# Teensylu.net
KiCad netlist of a schematic drawn in EAGLE
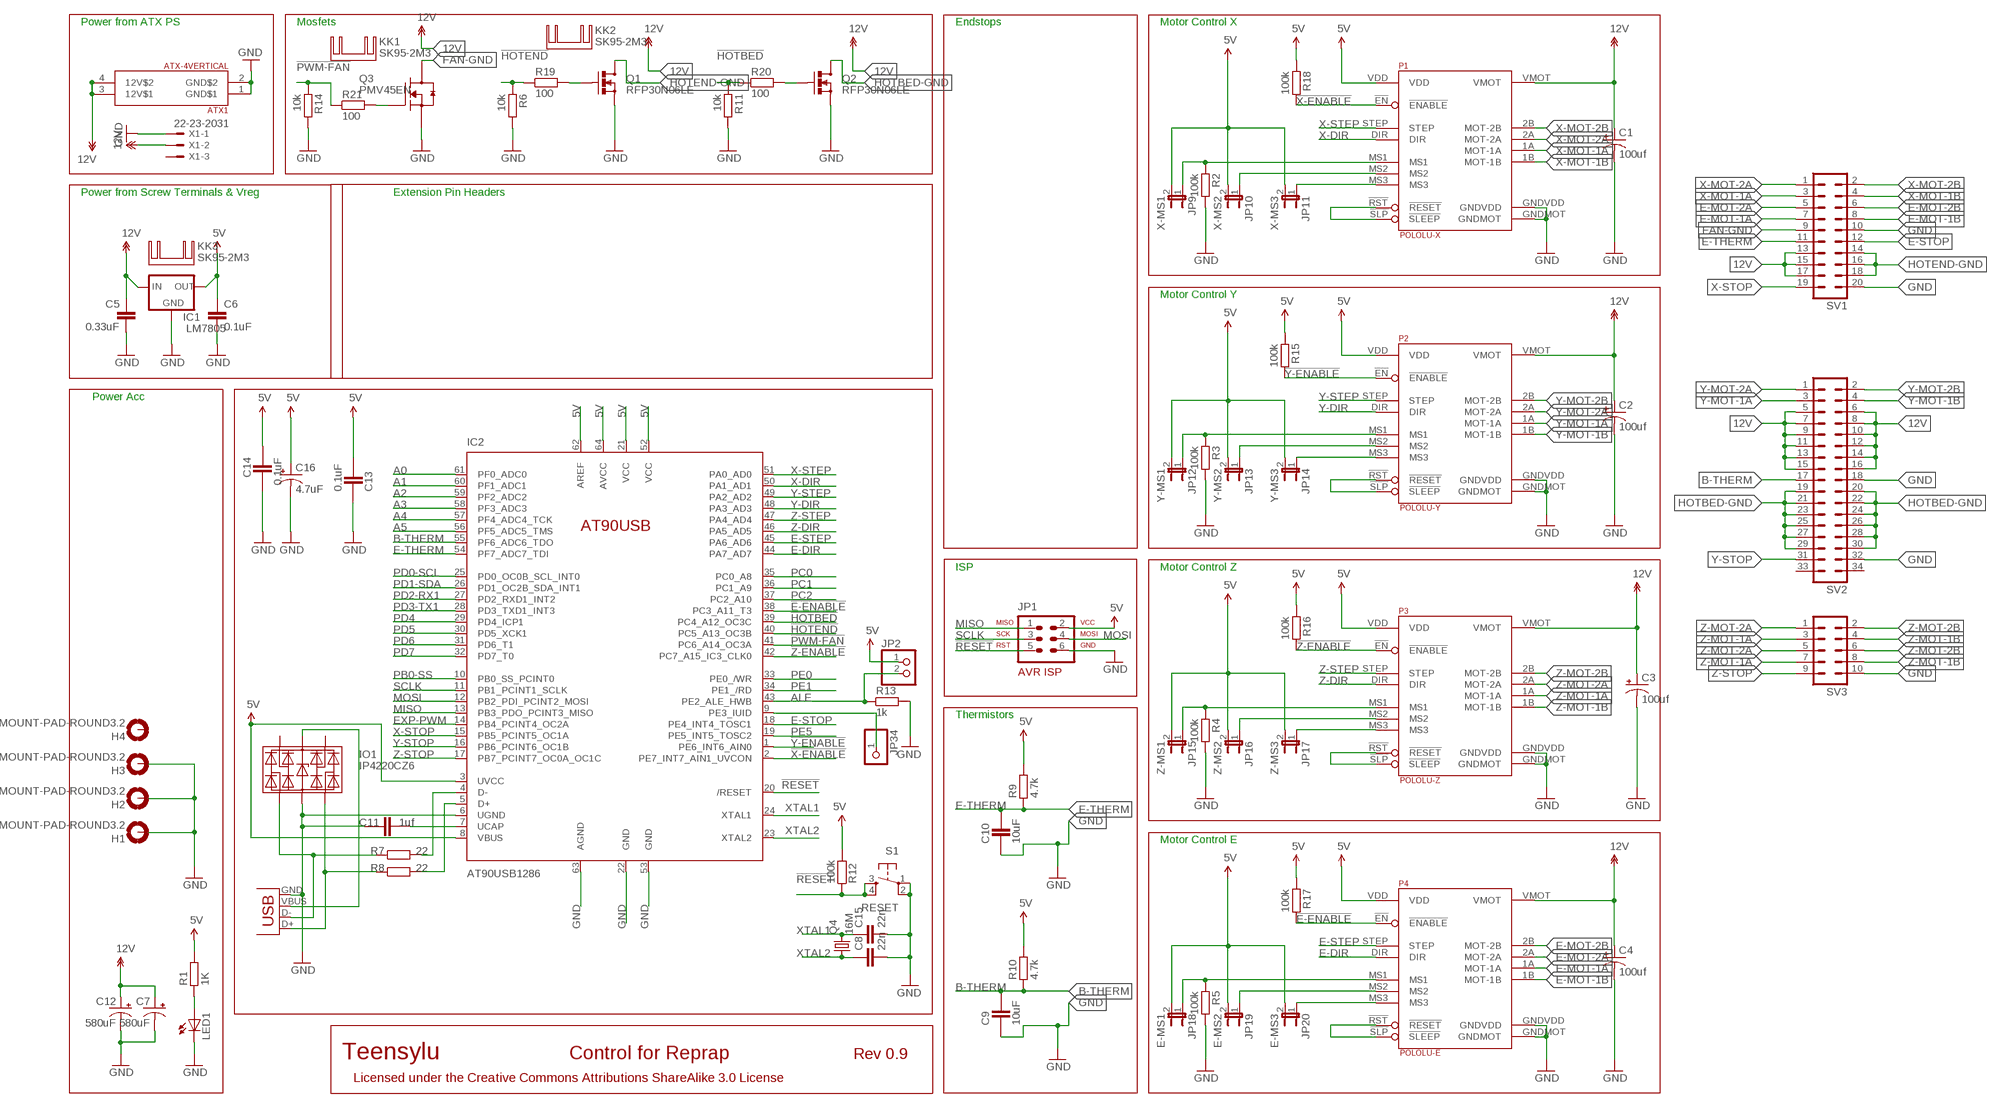
[diagram p0: schematic, sheet 1]

(export (version "E")
  (design (tool "Eeschema 10.0.6"))
  (components
    (comp (ref "ATX1")
      (value "ATX-4VERTICAL")
      (footprint "eagle-import:MINIFITJR-4-VERTICAL")
      (libsource (lib "eagle-import") (part "ATX-4VERTICAL"))
    )
    (comp (ref "C1")
      (value "100uf")
      (footprint "eagle-import:CPOL-RADIAL-100UF-25V")
      (libsource (lib "eagle-import") (part "CAP_POLPTH1"))
    )
    (comp (ref "C2")
      (value "100uf")
      (footprint "eagle-import:CPOL-RADIAL-100UF-25V")
      (libsource (lib "eagle-import") (part "CAP_POLPTH1"))
    )
    (comp (ref "C3")
      (value "100uf")
      (footprint "eagle-import:CPOL-RADIAL-100UF-25V")
      (libsource (lib "eagle-import") (part "CAP_POLPTH1"))
    )
    (comp (ref "C4")
      (value "100uf")
      (footprint "eagle-import:CPOL-RADIAL-100UF-25V")
      (libsource (lib "eagle-import") (part "CAP_POLPTH1"))
    )
    (comp (ref "C5")
      (value "0.33uF")
      (footprint "eagle-import:CAP-PTH-SMALL2")
      (libsource (lib "eagle-import") (part "CAPPTH2"))
    )
    (comp (ref "C6")
      (value "0.1uF")
      (footprint "eagle-import:CAP-PTH-SMALL2")
      (libsource (lib "eagle-import") (part "CAPPTH2"))
    )
    (comp (ref "C7")
      (value "580uF")
      (footprint "eagle-import:CPOL-RADIAL-1000UF-25V")
      (libsource (lib "eagle-import") (part "CAP_POLPTH4"))
    )
    (comp (ref "C8")
      (value "22n")
      (footprint "eagle-import:C0603")
      (libsource (lib "eagle-import") (part "C-EUC0603"))
    )
    (comp (ref "C9")
      (value "10uF")
      (footprint "eagle-import:CAPC1608X92N")
      (libsource (lib "eagle-import") (part "CAPACITOR_0603"))
    )
    (comp (ref "C10")
      (value "10uF")
      (footprint "eagle-import:CAPC1608X92N")
      (libsource (lib "eagle-import") (part "CAPACITOR_0603"))
    )
    (comp (ref "C11")
      (value "1uf")
      (footprint "eagle-import:CAPC1608X92N")
      (libsource (lib "eagle-import") (part "CAPACITOR_0603"))
    )
    (comp (ref "C12")
      (value "580uF")
      (footprint "eagle-import:CPOL-RADIAL-1000UF-25V")
      (libsource (lib "eagle-import") (part "CAP_POLPTH4"))
    )
    (comp (ref "C13")
      (value "0.1uF")
      (footprint "eagle-import:CAPC1608X92N")
      (libsource (lib "eagle-import") (part "CAPACITOR_0603"))
    )
    (comp (ref "C14")
      (value "0.1uF")
      (footprint "eagle-import:CAPC1608X92N")
      (libsource (lib "eagle-import") (part "CAPACITOR_0603"))
    )
    (comp (ref "C15")
      (value "22n")
      (footprint "eagle-import:C0603")
      (libsource (lib "eagle-import") (part "C-EUC0603"))
    )
    (comp (ref "C16")
      (value "4.7uF")
      (footprint "eagle-import:CPOL-RADIAL-10UF-25V")
      (libsource (lib "eagle-import") (part "CAP_POLPTH2"))
    )
    (comp (ref "H1")
      (value "MOUNT-PAD-ROUND3.2")
      (footprint "eagle-import:3,2-PAD")
      (libsource (lib "eagle-import") (part "MOUNT-PAD-ROUND3.2"))
    )
    (comp (ref "H2")
      (value "MOUNT-PAD-ROUND3.2")
      (footprint "eagle-import:3,2-PAD")
      (libsource (lib "eagle-import") (part "MOUNT-PAD-ROUND3.2"))
    )
    (comp (ref "H3")
      (value "MOUNT-PAD-ROUND3.2")
      (footprint "eagle-import:3,2-PAD")
      (libsource (lib "eagle-import") (part "MOUNT-PAD-ROUND3.2"))
    )
    (comp (ref "H4")
      (value "MOUNT-PAD-ROUND3.2")
      (footprint "eagle-import:3,2-PAD")
      (libsource (lib "eagle-import") (part "MOUNT-PAD-ROUND3.2"))
    )
    (comp (ref "IC1")
      (value "LM7805")
      (footprint "eagle-import:78XXL-CUSTOM")
      (libsource (lib "eagle-import") (part "V_REG_78XX"))
    )
    (comp (ref "IC2")
      (value "AT90USB1286")
      (footprint "eagle-import:TQFP64-2")
      (libsource (lib "eagle-import") (part "AT90USB"))
    )
    (comp (ref "IO1")
      (value "IP4220CZ6")
      (footprint "eagle-import:SOT23-6")
      (libsource (lib "eagle-import") (part "IP4220CZ6"))
    )
    (comp (ref "J1")
      (value "USB")
      (footprint "eagle-import:USB-B-PTH")
      (libsource (lib "eagle-import") (part "USBPTH"))
    )
    (comp (ref "JP1")
      (value "AVR-ISP-6VERT")
      (footprint "eagle-import:AVR-ISP-6")
      (libsource (lib "eagle-import") (part "AVR-ISP-6VERT"))
    )
    (comp (ref "JP2")
      (value "PINHD-1X2")
      (footprint "eagle-import:1X02")
      (libsource (lib "eagle-import") (part "PINHD-1X2"))
    )
    (comp (ref "JP9")
      (value "X-MS1")
      (footprint "eagle-import:1X02")
      (libsource (lib "eagle-import") (part "JUMPER-2PTH"))
    )
    (comp (ref "JP10")
      (value "X-MS2")
      (footprint "eagle-import:1X02")
      (libsource (lib "eagle-import") (part "JUMPER-2PTH"))
    )
    (comp (ref "JP11")
      (value "X-MS3")
      (footprint "eagle-import:1X02")
      (libsource (lib "eagle-import") (part "JUMPER-2PTH"))
    )
    (comp (ref "JP12")
      (value "Y-MS1")
      (footprint "eagle-import:1X02")
      (libsource (lib "eagle-import") (part "JUMPER-2PTH"))
    )
    (comp (ref "JP13")
      (value "Y-MS2")
      (footprint "eagle-import:1X02")
      (libsource (lib "eagle-import") (part "JUMPER-2PTH"))
    )
    (comp (ref "JP14")
      (value "Y-MS3")
      (footprint "eagle-import:1X02")
      (libsource (lib "eagle-import") (part "JUMPER-2PTH"))
    )
    (comp (ref "JP15")
      (value "Z-MS1")
      (footprint "eagle-import:1X02")
      (libsource (lib "eagle-import") (part "JUMPER-2PTH"))
    )
    (comp (ref "JP16")
      (value "Z-MS2")
      (footprint "eagle-import:1X02")
      (libsource (lib "eagle-import") (part "JUMPER-2PTH"))
    )
    (comp (ref "JP17")
      (value "Z-MS3")
      (footprint "eagle-import:1X02")
      (libsource (lib "eagle-import") (part "JUMPER-2PTH"))
    )
    (comp (ref "JP18")
      (value "E-MS1")
      (footprint "eagle-import:1X02")
      (libsource (lib "eagle-import") (part "JUMPER-2PTH"))
    )
    (comp (ref "JP19")
      (value "E-MS2")
      (footprint "eagle-import:1X02")
      (libsource (lib "eagle-import") (part "JUMPER-2PTH"))
    )
    (comp (ref "JP20")
      (value "E-MS3")
      (footprint "eagle-import:1X02")
      (libsource (lib "eagle-import") (part "JUMPER-2PTH"))
    )
    (comp (ref "JP34")
      (value "PINHD-1X1")
      (footprint "eagle-import:1X01")
      (libsource (lib "eagle-import") (part "PINHD-1X1"))
    )
    (comp (ref "KK1")
      (value "SK95-2M3")
      (footprint "eagle-import:SK95-2M3")
      (libsource (lib "eagle-import") (part "SK95-2M3"))
    )
    (comp (ref "KK2")
      (value "SK95-2M3")
      (footprint "eagle-import:SK95-2M3")
      (libsource (lib "eagle-import") (part "SK95-2M3"))
    )
    (comp (ref "KK3")
      (value "SK95-2M3")
      (footprint "eagle-import:SK95-2M3")
      (libsource (lib "eagle-import") (part "SK95-2M3"))
    )
    (comp (ref "LED1")
      (value "LED5MM")
      (footprint "eagle-import:LED5MM")
      (libsource (lib "eagle-import") (part "LED5MM"))
    )
    (comp (ref "P1")
      (value "POLOLU-X")
      (footprint "eagle-import:POLOLU-ALLEGRO-PTH")
      (libsource (lib "eagle-import") (part "POLOLU-ALLEGRO"))
    )
    (comp (ref "P2")
      (value "POLOLU-Y")
      (footprint "eagle-import:POLOLU-ALLEGRO-PTH")
      (libsource (lib "eagle-import") (part "POLOLU-ALLEGRO"))
    )
    (comp (ref "P3")
      (value "POLOLU-Z")
      (footprint "eagle-import:POLOLU-ALLEGRO-PTH")
      (libsource (lib "eagle-import") (part "POLOLU-ALLEGRO"))
    )
    (comp (ref "P4")
      (value "POLOLU-E")
      (footprint "eagle-import:POLOLU-ALLEGRO-PTH")
      (libsource (lib "eagle-import") (part "POLOLU-ALLEGRO"))
    )
    (comp (ref "Q1")
      (value "RFP30N06LE")
      (footprint "eagle-import:TO220V")
      (libsource (lib "eagle-import") (part "MOSFET-NCHANNELPTH2"))
    )
    (comp (ref "Q2")
      (value "RFP30N06LE")
      (footprint "eagle-import:TO220V")
      (libsource (lib "eagle-import") (part "MOSFET-NCHANNELPTH2"))
    )
    (comp (ref "Q3")
      (value "PMV45EN")
      (footprint "eagle-import:SOT95P280X135-3N")
      (libsource (lib "eagle-import") (part "MOSFET-NCH_SOT-23"))
    )
    (comp (ref "Q4")
      (value "16M")
      (footprint "eagle-import:HC49U-V")
      (libsource (lib "eagle-import") (part "CRYSTALHC49U-V"))
    )
    (comp (ref "R1")
      (value "1K")
      (footprint "eagle-import:RESC1608X55N")
      (libsource (lib "eagle-import") (part "RESISTOR_0603"))
    )
    (comp (ref "R2")
      (value "100k")
      (footprint "eagle-import:RESC1608X55N")
      (libsource (lib "eagle-import") (part "RESISTOR_0603"))
    )
    (comp (ref "R3")
      (value "100k")
      (footprint "eagle-import:RESC1608X55N")
      (libsource (lib "eagle-import") (part "RESISTOR_0603"))
    )
    (comp (ref "R4")
      (value "100k")
      (footprint "eagle-import:RESC1608X55N")
      (libsource (lib "eagle-import") (part "RESISTOR_0603"))
    )
    (comp (ref "R5")
      (value "100k")
      (footprint "eagle-import:RESC1608X55N")
      (libsource (lib "eagle-import") (part "RESISTOR_0603"))
    )
    (comp (ref "R6")
      (value "10k")
      (footprint "eagle-import:RESC1608X55N")
      (libsource (lib "eagle-import") (part "RESISTOR_0603"))
    )
    (comp (ref "R7")
      (value "22")
      (footprint "eagle-import:RESC1608X55N")
      (libsource (lib "eagle-import") (part "RESISTOR_0603"))
    )
    (comp (ref "R8")
      (value "22")
      (footprint "eagle-import:RESC1608X55N")
      (libsource (lib "eagle-import") (part "RESISTOR_0603"))
    )
    (comp (ref "R9")
      (value "4.7k")
      (footprint "eagle-import:RESC1608X55N")
      (libsource (lib "eagle-import") (part "RESISTOR_0603"))
    )
    (comp (ref "R10")
      (value "4.7k")
      (footprint "eagle-import:RESC1608X55N")
      (libsource (lib "eagle-import") (part "RESISTOR_0603"))
    )
    (comp (ref "R11")
      (value "10k")
      (footprint "eagle-import:RESC1608X55N")
      (libsource (lib "eagle-import") (part "RESISTOR_0603"))
    )
    (comp (ref "R12")
      (value "100k")
      (footprint "eagle-import:RESC1608X55N")
      (libsource (lib "eagle-import") (part "RESISTOR_0603"))
    )
    (comp (ref "R13")
      (value "1k")
      (footprint "eagle-import:RESC1608X55N")
      (libsource (lib "eagle-import") (part "RESISTOR_0603"))
    )
    (comp (ref "R14")
      (value "10k")
      (footprint "eagle-import:RESC1608X55N")
      (libsource (lib "eagle-import") (part "RESISTOR_0603"))
    )
    (comp (ref "R15")
      (value "100k")
      (footprint "eagle-import:RESC1608X55N")
      (libsource (lib "eagle-import") (part "RESISTOR_0603"))
    )
    (comp (ref "R16")
      (value "100k")
      (footprint "eagle-import:RESC1608X55N")
      (libsource (lib "eagle-import") (part "RESISTOR_0603"))
    )
    (comp (ref "R17")
      (value "100k")
      (footprint "eagle-import:RESC1608X55N")
      (libsource (lib "eagle-import") (part "RESISTOR_0603"))
    )
    (comp (ref "R18")
      (value "100k")
      (footprint "eagle-import:RESC1608X55N")
      (libsource (lib "eagle-import") (part "RESISTOR_0603"))
    )
    (comp (ref "R19")
      (value "100")
      (footprint "eagle-import:RESC1608X55N")
      (libsource (lib "eagle-import") (part "RESISTOR_0603"))
    )
    (comp (ref "R20")
      (value "100")
      (footprint "eagle-import:RESC1608X55N")
      (libsource (lib "eagle-import") (part "RESISTOR_0603"))
    )
    (comp (ref "R21")
      (value "100")
      (footprint "eagle-import:RESC1608X55N")
      (libsource (lib "eagle-import") (part "RESISTOR_0603"))
    )
    (comp (ref "S1")
      (value "RESET")
      (footprint "eagle-import:TACTILE-PTH")
      (libsource (lib "eagle-import") (part "TAC_SWITCHPTH"))
    )
    (comp (ref "SV1")
      (value "ML20L")
      (footprint "eagle-import:ML20L")
      (libsource (lib "eagle-import") (part "ML20L"))
    )
    (comp (ref "SV2")
      (value "ML34L")
      (footprint "eagle-import:ML34L")
      (libsource (lib "eagle-import") (part "ML34L"))
    )
    (comp (ref "SV3")
      (value "ML10L")
      (footprint "eagle-import:ML10L")
      (libsource (lib "eagle-import") (part "ML10L"))
    )
    (comp (ref "X1")
      (value "22-23-2031")
      (footprint "eagle-import:22-23-2031")
      (fields (field (name "MF") "MOLEX"))
      (libsource (lib "eagle-import") (part "22-23-2031"))
    )
  )
  (nets
    (net (code "1") (name "/A0") (class "Default")
      (node (ref "IC2") (pin "61") (pinfunction "PF0_ADC0_61") (pintype "bidirectional"))
    )
    (net (code "2") (name "/A1") (class "Default")
      (node (ref "IC2") (pin "60") (pinfunction "PF1_ADC1_60") (pintype "bidirectional"))
    )
    (net (code "3") (name "/A2") (class "Default")
      (node (ref "IC2") (pin "59") (pinfunction "PF2_ADC2_59") (pintype "bidirectional"))
    )
    (net (code "4") (name "/A3") (class "Default")
      (node (ref "IC2") (pin "58") (pinfunction "PF3_ADC3_58") (pintype "bidirectional"))
    )
    (net (code "5") (name "/A4") (class "Default")
      (node (ref "IC2") (pin "57") (pinfunction "PF4_ADC4_TCK_57") (pintype "bidirectional"))
    )
    (net (code "6") (name "/A5") (class "Default")
      (node (ref "IC2") (pin "56") (pinfunction "PF5_ADC5_TMS_56") (pintype "bidirectional"))
    )
    (net (code "7") (name "/ALE") (class "Default")
      (node (ref "IC2") (pin "43") (pinfunction "PE2_ALE_HWB_43") (pintype "bidirectional"))
      (node (ref "JP2") (pin "2") (pinfunction "2_2") (pintype "passive"))
      (node (ref "R13") (pin "1") (pinfunction "1_1") (pintype "passive"))
    )
    (net (code "8") (name "/E-DIR") (class "Default")
      (node (ref "IC2") (pin "44") (pinfunction "PA7_AD7_44") (pintype "bidirectional"))
      (node (ref "P4") (pin "DIR") (pinfunction "DIR_DIR") (pintype "bidirectional"))
    )
    (net (code "9") (name "/E-STEP") (class "Default")
      (node (ref "IC2") (pin "45") (pinfunction "PA6_AD6_45") (pintype "bidirectional"))
      (node (ref "P4") (pin "STEP") (pinfunction "STEP_STEP") (pintype "bidirectional"))
    )
    (net (code "10") (name "/EXP-PWM") (class "Default")
      (node (ref "IC2") (pin "14") (pinfunction "PB4_PCINT4_OC2A_14") (pintype "bidirectional"))
    )
    (net (code "11") (name "/MISO") (class "Default")
      (node (ref "IC2") (pin "13") (pinfunction "PB3_PDO_PCINT3_MISO_13") (pintype "bidirectional"))
      (node (ref "JP1") (pin "1") (pinfunction "1_1") (pintype "passive"))
    )
    (net (code "12") (name "/MOSI") (class "Default")
      (node (ref "IC2") (pin "12") (pinfunction "PB2_PDI_PCINT2_MOSI_12") (pintype "bidirectional"))
      (node (ref "JP1") (pin "4") (pinfunction "4_4") (pintype "passive"))
    )
    (net (code "13") (name "/PB0-SS") (class "Default")
      (node (ref "IC2") (pin "10") (pinfunction "PB0_SS_PCINT0_10") (pintype "bidirectional"))
    )
    (net (code "14") (name "/PC0") (class "Default")
      (node (ref "IC2") (pin "35") (pinfunction "PC0_A8_35") (pintype "bidirectional"))
    )
    (net (code "15") (name "/PC1") (class "Default")
      (node (ref "IC2") (pin "36") (pinfunction "PC1_A9_36") (pintype "bidirectional"))
    )
    (net (code "16") (name "/PC2") (class "Default")
      (node (ref "IC2") (pin "37") (pinfunction "PC2_A10_37") (pintype "bidirectional"))
    )
    (net (code "17") (name "/PD0-SCL") (class "Default")
      (node (ref "IC2") (pin "25") (pinfunction "PD0_OC0B_SCL_INT0_25") (pintype "bidirectional"))
    )
    (net (code "18") (name "/PD1-SDA") (class "Default")
      (node (ref "IC2") (pin "26") (pinfunction "PD1_OC2B_SDA_INT1_26") (pintype "bidirectional"))
    )
    (net (code "19") (name "/PD2-RX1") (class "Default")
      (node (ref "IC2") (pin "27") (pinfunction "PD2_RXD1_INT2_27") (pintype "bidirectional"))
    )
    (net (code "20") (name "/PD3-TX1") (class "Default")
      (node (ref "IC2") (pin "28") (pinfunction "PD3_TXD1_INT3_28") (pintype "bidirectional"))
    )
    (net (code "21") (name "/PD4") (class "Default")
      (node (ref "IC2") (pin "29") (pinfunction "PD4_ICP1_29") (pintype "bidirectional"))
    )
    (net (code "22") (name "/PD5") (class "Default")
      (node (ref "IC2") (pin "30") (pinfunction "PD5_XCK1_30") (pintype "bidirectional"))
    )
    (net (code "23") (name "/PD6") (class "Default")
      (node (ref "IC2") (pin "31") (pinfunction "PD6_T1_31") (pintype "bidirectional"))
    )
    (net (code "24") (name "/PD7") (class "Default")
      (node (ref "IC2") (pin "32") (pinfunction "PD7_T0_32") (pintype "bidirectional"))
    )
    (net (code "25") (name "/PE0") (class "Default")
      (node (ref "IC2") (pin "33") (pinfunction "PE0_/WR_33") (pintype "bidirectional"))
    )
    (net (code "26") (name "/PE1") (class "Default")
      (node (ref "IC2") (pin "34") (pinfunction "PE1_/RD_34") (pintype "bidirectional"))
    )
    (net (code "27") (name "/PE5") (class "Default")
      (node (ref "IC2") (pin "19") (pinfunction "PE5_INT5_TOSC2_19") (pintype "bidirectional"))
    )
    (net (code "28") (name "/SCLK") (class "Default")
      (node (ref "IC2") (pin "11") (pinfunction "PB1_PCINT1_SCLK_11") (pintype "bidirectional"))
      (node (ref "JP1") (pin "3") (pinfunction "3_3") (pintype "passive"))
    )
    (net (code "29") (name "/X-DIR") (class "Default")
      (node (ref "IC2") (pin "50") (pinfunction "PA1_AD1_50") (pintype "bidirectional"))
      (node (ref "P1") (pin "DIR") (pinfunction "DIR_DIR") (pintype "bidirectional"))
    )
    (net (code "30") (name "/X-STEP") (class "Default")
      (node (ref "IC2") (pin "51") (pinfunction "PA0_AD0_51") (pintype "bidirectional"))
      (node (ref "P1") (pin "STEP") (pinfunction "STEP_STEP") (pintype "bidirectional"))
    )
    (net (code "31") (name "/XTAL1") (class "Default")
      (node (ref "C15") (pin "1") (pinfunction "1_1") (pintype "passive"))
      (node (ref "IC2") (pin "24") (pinfunction "XTAL1_24") (pintype "passive"))
      (node (ref "Q4") (pin "2") (pinfunction "2_2") (pintype "passive"))
    )
    (net (code "32") (name "/XTAL2") (class "Default")
      (node (ref "C8") (pin "1") (pinfunction "1_1") (pintype "passive"))
      (node (ref "IC2") (pin "23") (pinfunction "XTAL2_23") (pintype "passive"))
      (node (ref "Q4") (pin "1") (pinfunction "1_1") (pintype "passive"))
    )
    (net (code "33") (name "/Y-DIR") (class "Default")
      (node (ref "IC2") (pin "48") (pinfunction "PA3_AD3_48") (pintype "bidirectional"))
      (node (ref "P2") (pin "DIR") (pinfunction "DIR_DIR") (pintype "bidirectional"))
    )
    (net (code "34") (name "/Y-STEP") (class "Default")
      (node (ref "IC2") (pin "49") (pinfunction "PA2_AD2_49") (pintype "bidirectional"))
      (node (ref "P2") (pin "STEP") (pinfunction "STEP_STEP") (pintype "bidirectional"))
    )
    (net (code "35") (name "/Z-DIR") (class "Default")
      (node (ref "IC2") (pin "46") (pinfunction "PA5_AD5_46") (pintype "bidirectional"))
      (node (ref "P3") (pin "DIR") (pinfunction "DIR_DIR") (pintype "bidirectional"))
    )
    (net (code "36") (name "/Z-STEP") (class "Default")
      (node (ref "IC2") (pin "47") (pinfunction "PA4_AD4_47") (pintype "bidirectional"))
      (node (ref "P3") (pin "STEP") (pinfunction "STEP_STEP") (pintype "bidirectional"))
    )
    (net (code "37") (name "/~{E-ENABLE}") (class "Default")
      (node (ref "IC2") (pin "38") (pinfunction "PC3_A11_T3_38") (pintype "bidirectional"))
      (node (ref "P4") (pin "!EN") (pinfunction "~{ENABLE}_!EN") (pintype "input"))
      (node (ref "R17") (pin "2") (pinfunction "2_2") (pintype "passive"))
    )
    (net (code "38") (name "/~{HOTBED}") (class "Default")
      (node (ref "IC2") (pin "39") (pinfunction "PC4_A12_OC3C_39") (pintype "bidirectional"))
      (node (ref "R11") (pin "1") (pinfunction "1_1") (pintype "passive"))
      (node (ref "R20") (pin "1") (pinfunction "1_1") (pintype "passive"))
    )
    (net (code "39") (name "/~{HOTEND}") (class "Default")
      (node (ref "IC2") (pin "40") (pinfunction "PC5_A13_OC3B_40") (pintype "bidirectional"))
      (node (ref "R19") (pin "1") (pinfunction "1_1") (pintype "passive"))
      (node (ref "R6") (pin "1") (pinfunction "1_1") (pintype "passive"))
    )
    (net (code "40") (name "/~{PWM-FAN}") (class "Default")
      (node (ref "IC2") (pin "41") (pinfunction "PC6_A14_OC3A_41") (pintype "bidirectional"))
      (node (ref "R14") (pin "1") (pinfunction "1_1") (pintype "passive"))
      (node (ref "R21") (pin "1") (pinfunction "1_1") (pintype "passive"))
    )
    (net (code "41") (name "/~{RESET}") (class "Default")
      (node (ref "IC2") (pin "20") (pinfunction "/RESET_20") (pintype "bidirectional"))
      (node (ref "JP1") (pin "5") (pinfunction "5_5") (pintype "passive"))
      (node (ref "R12") (pin "1") (pinfunction "1_1") (pintype "passive"))
      (node (ref "S1") (pin "3") (pinfunction "3_3") (pintype "passive"))
      (node (ref "S1") (pin "4") (pinfunction "4_4") (pintype "passive"))
    )
    (net (code "42") (name "/~{X-ENABLE}") (class "Default")
      (node (ref "IC2") (pin "2") (pinfunction "PE7_INT7_AIN1_UVCON_2") (pintype "bidirectional"))
      (node (ref "P1") (pin "!EN") (pinfunction "~{ENABLE}_!EN") (pintype "input"))
      (node (ref "R18") (pin "2") (pinfunction "2_2") (pintype "passive"))
    )
    (net (code "43") (name "/~{Y-ENABLE}") (class "Default")
      (node (ref "IC2") (pin "1") (pinfunction "PE6_INT6_AIN0_1") (pintype "bidirectional"))
      (node (ref "P2") (pin "!EN") (pinfunction "~{ENABLE}_!EN") (pintype "input"))
      (node (ref "R15") (pin "2") (pinfunction "2_2") (pintype "passive"))
    )
    (net (code "44") (name "/~{Z-ENABLE}") (class "Default")
      (node (ref "IC2") (pin "42") (pinfunction "PC7_A15_IC3_CLK0_42") (pintype "bidirectional"))
      (node (ref "P3") (pin "!EN") (pinfunction "~{ENABLE}_!EN") (pintype "input"))
      (node (ref "R16") (pin "2") (pinfunction "2_2") (pintype "passive"))
    )
    (net (code "45") (name "5V") (class "Default")
      (node (ref "C13") (pin "2") (pinfunction "2_2") (pintype "passive"))
      (node (ref "C14") (pin "1") (pinfunction "1_1") (pintype "passive"))
      (node (ref "C16") (pin "1") (pinfunction "+_1") (pintype "passive"))
      (node (ref "C6") (pin "1") (pinfunction "1_1") (pintype "passive"))
      (node (ref "IC1") (pin "OUT") (pinfunction "OUT_OUT") (pintype "output"))
      (node (ref "IC2") (pin "21") (pinfunction "VCC_21") (pintype "power_in"))
      (node (ref "IC2") (pin "3") (pinfunction "UVCC_3") (pintype "power_in"))
      (node (ref "IC2") (pin "52") (pinfunction "VCC_52") (pintype "power_in"))
      (node (ref "IC2") (pin "62") (pinfunction "AREF_62") (pintype "power_in"))
      (node (ref "IC2") (pin "64") (pinfunction "AVCC_64") (pintype "power_in"))
      (node (ref "IC2") (pin "8") (pinfunction "VBUS_8") (pintype "bidirectional"))
      (node (ref "JP1") (pin "2") (pinfunction "2_2") (pintype "passive"))
      (node (ref "JP10") (pin "2") (pinfunction "2_2") (pintype "passive"))
      (node (ref "JP11") (pin "2") (pinfunction "2_2") (pintype "passive"))
      (node (ref "JP12") (pin "2") (pinfunction "2_2") (pintype "passive"))
      (node (ref "JP13") (pin "2") (pinfunction "2_2") (pintype "passive"))
      (node (ref "JP14") (pin "2") (pinfunction "2_2") (pintype "passive"))
      (node (ref "JP15") (pin "2") (pinfunction "2_2") (pintype "passive"))
      (node (ref "JP16") (pin "2") (pinfunction "2_2") (pintype "passive"))
      (node (ref "JP17") (pin "2") (pinfunction "2_2") (pintype "passive"))
      (node (ref "JP18") (pin "2") (pinfunction "2_2") (pintype "passive"))
      (node (ref "JP19") (pin "2") (pinfunction "2_2") (pintype "passive"))
      (node (ref "JP2") (pin "1") (pinfunction "1_1") (pintype "passive"))
      (node (ref "JP20") (pin "2") (pinfunction "2_2") (pintype "passive"))
      (node (ref "JP9") (pin "2") (pinfunction "2_2") (pintype "passive"))
      (node (ref "P1") (pin "VDD") (pinfunction "VDD_VDD") (pintype "power_in"))
      (node (ref "P2") (pin "VDD") (pinfunction "VDD_VDD") (pintype "power_in"))
      (node (ref "P3") (pin "VDD") (pinfunction "VDD_VDD") (pintype "power_in"))
      (node (ref "P4") (pin "VDD") (pinfunction "VDD_VDD") (pintype "power_in"))
      (node (ref "R1") (pin "2") (pinfunction "2_2") (pintype "passive"))
      (node (ref "R10") (pin "2") (pinfunction "2_2") (pintype "passive"))
      (node (ref "R12") (pin "2") (pinfunction "2_2") (pintype "passive"))
      (node (ref "R15") (pin "1") (pinfunction "1_1") (pintype "passive"))
      (node (ref "R16") (pin "1") (pinfunction "1_1") (pintype "passive"))
      (node (ref "R17") (pin "1") (pinfunction "1_1") (pintype "passive"))
      (node (ref "R18") (pin "1") (pinfunction "1_1") (pintype "passive"))
      (node (ref "R9") (pin "2") (pinfunction "2_2") (pintype "passive"))
    )
    (net (code "46") (name "12V") (class "Default")
      (node (ref "ATX1") (pin "3") (pinfunction "12V$1_3") (pintype "power_in"))
      (node (ref "ATX1") (pin "4") (pinfunction "12V$2_4") (pintype "power_in"))
      (node (ref "C1") (pin "1") (pinfunction "+_1") (pintype "passive"))
      (node (ref "C12") (pin "1") (pinfunction "+_1") (pintype "passive"))
      (node (ref "C2") (pin "1") (pinfunction "+_1") (pintype "passive"))
      (node (ref "C3") (pin "1") (pinfunction "+_1") (pintype "passive"))
      (node (ref "C4") (pin "1") (pinfunction "+_1") (pintype "passive"))
      (node (ref "C5") (pin "1") (pinfunction "1_1") (pintype "passive"))
      (node (ref "C7") (pin "1") (pinfunction "+_1") (pintype "passive"))
      (node (ref "IC1") (pin "IN") (pinfunction "IN_IN") (pintype "input"))
      (node (ref "P1") (pin "VMOT") (pinfunction "VMOT_VMOT") (pintype "power_in"))
      (node (ref "P2") (pin "VMOT") (pinfunction "VMOT_VMOT") (pintype "power_in"))
      (node (ref "P3") (pin "VMOT") (pinfunction "VMOT_VMOT") (pintype "power_in"))
      (node (ref "P4") (pin "VMOT") (pinfunction "VMOT_VMOT") (pintype "power_in"))
      (node (ref "SV1") (pin "13") (pinfunction "13_13") (pintype "passive"))
      (node (ref "SV1") (pin "15") (pinfunction "15_15") (pintype "passive"))
      (node (ref "SV1") (pin "17") (pinfunction "17_17") (pintype "passive"))
      (node (ref "SV2") (pin "10") (pinfunction "10_10") (pintype "passive"))
      (node (ref "SV2") (pin "11") (pinfunction "11_11") (pintype "passive"))
      (node (ref "SV2") (pin "12") (pinfunction "12_12") (pintype "passive"))
      (node (ref "SV2") (pin "13") (pinfunction "13_13") (pintype "passive"))
      (node (ref "SV2") (pin "14") (pinfunction "14_14") (pintype "passive"))
      (node (ref "SV2") (pin "15") (pinfunction "15_15") (pintype "passive"))
      (node (ref "SV2") (pin "16") (pinfunction "16_16") (pintype "passive"))
      (node (ref "SV2") (pin "5") (pinfunction "5_5") (pintype "passive"))
      (node (ref "SV2") (pin "6") (pinfunction "6_6") (pintype "passive"))
      (node (ref "SV2") (pin "7") (pinfunction "7_7") (pintype "passive"))
      (node (ref "SV2") (pin "8") (pinfunction "8_8") (pintype "passive"))
      (node (ref "SV2") (pin "9") (pinfunction "9_9") (pintype "passive"))
      (node (ref "X1") (pin "2") (pinfunction "S_2") (pintype "passive"))
    )
    (net (code "47") (name "B-THERM") (class "Default")
      (node (ref "C9") (pin "2") (pinfunction "2_2") (pintype "passive"))
      (node (ref "IC2") (pin "55") (pinfunction "PF6_ADC6_TDO_55") (pintype "bidirectional"))
      (node (ref "R10") (pin "1") (pinfunction "1_1") (pintype "passive"))
      (node (ref "SV2") (pin "17") (pinfunction "17_17") (pintype "passive"))
    )
    (net (code "48") (name "E-MOT-1A") (class "Default")
      (node (ref "P4") (pin "1A") (pinfunction "MOT-1A_1A") (pintype "power_in"))
      (node (ref "SV1") (pin "7") (pinfunction "7_7") (pintype "passive"))
    )
    (net (code "49") (name "E-MOT-1B") (class "Default")
      (node (ref "P4") (pin "1B") (pinfunction "MOT-1B_1B") (pintype "power_in"))
      (node (ref "SV1") (pin "8") (pinfunction "8_8") (pintype "passive"))
    )
    (net (code "50") (name "E-MOT-2A") (class "Default")
      (node (ref "P4") (pin "2A") (pinfunction "MOT-2A_2A") (pintype "power_in"))
      (node (ref "SV1") (pin "5") (pinfunction "5_5") (pintype "passive"))
    )
    (net (code "51") (name "E-MOT-2B") (class "Default")
      (node (ref "P4") (pin "2B") (pinfunction "MOT-2B_2B") (pintype "power_in"))
      (node (ref "SV1") (pin "6") (pinfunction "6_6") (pintype "passive"))
    )
    (net (code "52") (name "E-STOP") (class "Default")
      (node (ref "IC2") (pin "18") (pinfunction "PE4_INT4_TOSC1_18") (pintype "bidirectional"))
      (node (ref "SV1") (pin "12") (pinfunction "12_12") (pintype "passive"))
    )
    (net (code "53") (name "E-THERM") (class "Default")
      (node (ref "C10") (pin "2") (pinfunction "2_2") (pintype "passive"))
      (node (ref "IC2") (pin "54") (pinfunction "PF7_ADC7_TDI_54") (pintype "bidirectional"))
      (node (ref "R9") (pin "1") (pinfunction "1_1") (pintype "passive"))
      (node (ref "SV1") (pin "11") (pinfunction "11_11") (pintype "passive"))
    )
    (net (code "54") (name "FAN-GND") (class "Default")
      (node (ref "Q3") (pin "3") (pinfunction "D_3") (pintype "passive"))
      (node (ref "SV1") (pin "9") (pinfunction "9_9") (pintype "passive"))
    )
    (net (code "55") (name "GND") (class "Default")
      (node (ref "ATX1") (pin "1") (pinfunction "GND$1_1") (pintype "power_in"))
      (node (ref "ATX1") (pin "2") (pinfunction "GND$2_2") (pintype "power_in"))
      (node (ref "C1") (pin "2") (pinfunction "-_2") (pintype "passive"))
      (node (ref "C10") (pin "1") (pinfunction "1_1") (pintype "passive"))
      (node (ref "C11") (pin "1") (pinfunction "1_1") (pintype "passive"))
      (node (ref "C12") (pin "2") (pinfunction "-_2") (pintype "passive"))
      (node (ref "C13") (pin "1") (pinfunction "1_1") (pintype "passive"))
      (node (ref "C14") (pin "2") (pinfunction "2_2") (pintype "passive"))
      (node (ref "C15") (pin "2") (pinfunction "2_2") (pintype "passive"))
      (node (ref "C16") (pin "2") (pinfunction "-_2") (pintype "passive"))
      (node (ref "C2") (pin "2") (pinfunction "-_2") (pintype "passive"))
      (node (ref "C3") (pin "2") (pinfunction "-_2") (pintype "passive"))
      (node (ref "C4") (pin "2") (pinfunction "-_2") (pintype "passive"))
      (node (ref "C5") (pin "2") (pinfunction "2_2") (pintype "passive"))
      (node (ref "C6") (pin "2") (pinfunction "2_2") (pintype "passive"))
      (node (ref "C7") (pin "2") (pinfunction "-_2") (pintype "passive"))
      (node (ref "C8") (pin "2") (pinfunction "2_2") (pintype "passive"))
      (node (ref "C9") (pin "1") (pinfunction "1_1") (pintype "passive"))
      (node (ref "H1") (pin "B3,2") (pinfunction "MOUNT_B3,2") (pintype "passive"))
      (node (ref "H2") (pin "B3,2") (pinfunction "MOUNT_B3,2") (pintype "passive"))
      (node (ref "H3") (pin "B3,2") (pinfunction "MOUNT_B3,2") (pintype "passive"))
      (node (ref "IC1") (pin "GND") (pinfunction "GND_GND") (pintype "input"))
      (node (ref "IC2") (pin "22") (pinfunction "GND_22") (pintype "power_in"))
      (node (ref "IC2") (pin "53") (pinfunction "GND_53") (pintype "power_in"))
      (node (ref "IC2") (pin "6") (pinfunction "UGND_6") (pintype "power_in"))
      (node (ref "IC2") (pin "63") (pinfunction "AGND_63") (pintype "power_in"))
      (node (ref "IO1") (pin "2") (pinfunction "GND_2") (pintype "bidirectional"))
      (node (ref "J1") (pin "GND") (pinfunction "GND_GND") (pintype "bidirectional"))
      (node (ref "JP1") (pin "6") (pinfunction "6_6") (pintype "passive"))
      (node (ref "LED1") (pin "K") (pinfunction "C_K") (pintype "passive"))
      (node (ref "P1") (pin "GNDMOT") (pinfunction "GNDMOT_GNDMOT") (pintype "power_in"))
      (node (ref "P1") (pin "GNDVDD") (pinfunction "GNDVDD_GNDVDD") (pintype "power_in"))
      (node (ref "P2") (pin "GNDMOT") (pinfunction "GNDMOT_GNDMOT") (pintype "power_in"))
      (node (ref "P2") (pin "GNDVDD") (pinfunction "GNDVDD_GNDVDD") (pintype "power_in"))
      (node (ref "P3") (pin "GNDMOT") (pinfunction "GNDMOT_GNDMOT") (pintype "power_in"))
      (node (ref "P3") (pin "GNDVDD") (pinfunction "GNDVDD_GNDVDD") (pintype "power_in"))
      (node (ref "P4") (pin "GNDMOT") (pinfunction "GNDMOT_GNDMOT") (pintype "power_in"))
      (node (ref "P4") (pin "GNDVDD") (pinfunction "GNDVDD_GNDVDD") (pintype "power_in"))
      (node (ref "Q1") (pin "3") (pinfunction "S_3") (pintype "passive"))
      (node (ref "Q2") (pin "3") (pinfunction "S_3") (pintype "passive"))
      (node (ref "Q3") (pin "2") (pinfunction "S_2") (pintype "passive"))
      (node (ref "R11") (pin "2") (pinfunction "2_2") (pintype "passive"))
      (node (ref "R13") (pin "2") (pinfunction "2_2") (pintype "passive"))
      (node (ref "R14") (pin "2") (pinfunction "2_2") (pintype "passive"))
      (node (ref "R2") (pin "2") (pinfunction "2_2") (pintype "passive"))
      (node (ref "R3") (pin "2") (pinfunction "2_2") (pintype "passive"))
      (node (ref "R4") (pin "2") (pinfunction "2_2") (pintype "passive"))
      (node (ref "R5") (pin "2") (pinfunction "2_2") (pintype "passive"))
      (node (ref "R6") (pin "2") (pinfunction "2_2") (pintype "passive"))
      (node (ref "S1") (pin "1") (pinfunction "1_1") (pintype "passive"))
      (node (ref "S1") (pin "2") (pinfunction "2_2") (pintype "passive"))
      (node (ref "SV1") (pin "10") (pinfunction "10_10") (pintype "passive"))
      (node (ref "SV1") (pin "20") (pinfunction "20_20") (pintype "passive"))
      (node (ref "SV2") (pin "18") (pinfunction "18_18") (pintype "passive"))
      (node (ref "SV2") (pin "32") (pinfunction "32_32") (pintype "passive"))
      (node (ref "SV3") (pin "10") (pinfunction "10_10") (pintype "passive"))
      (node (ref "X1") (pin "1") (pinfunction "S_1") (pintype "passive"))
    )
    (net (code "56") (name "HOTBED-GND") (class "Default")
      (node (ref "Q2") (pin "2") (pinfunction "D_2") (pintype "passive"))
      (node (ref "SV2") (pin "19") (pinfunction "19_19") (pintype "passive"))
      (node (ref "SV2") (pin "20") (pinfunction "20_20") (pintype "passive"))
      (node (ref "SV2") (pin "21") (pinfunction "21_21") (pintype "passive"))
      (node (ref "SV2") (pin "22") (pinfunction "22_22") (pintype "passive"))
      (node (ref "SV2") (pin "23") (pinfunction "23_23") (pintype "passive"))
      (node (ref "SV2") (pin "24") (pinfunction "24_24") (pintype "passive"))
      (node (ref "SV2") (pin "25") (pinfunction "25_25") (pintype "passive"))
      (node (ref "SV2") (pin "26") (pinfunction "26_26") (pintype "passive"))
      (node (ref "SV2") (pin "27") (pinfunction "27_27") (pintype "passive"))
      (node (ref "SV2") (pin "28") (pinfunction "28_28") (pintype "passive"))
      (node (ref "SV2") (pin "29") (pinfunction "29_29") (pintype "passive"))
      (node (ref "SV2") (pin "30") (pinfunction "30_30") (pintype "passive"))
    )
    (net (code "57") (name "HOTEND-GND") (class "Default")
      (node (ref "Q1") (pin "2") (pinfunction "D_2") (pintype "passive"))
      (node (ref "SV1") (pin "14") (pinfunction "14_14") (pintype "passive"))
      (node (ref "SV1") (pin "16") (pinfunction "16_16") (pintype "passive"))
      (node (ref "SV1") (pin "18") (pinfunction "18_18") (pintype "passive"))
    )
    (net (code "58") (name "Net-(IC2-D+)") (class "Default")
      (node (ref "IC2") (pin "5") (pinfunction "D+_5") (pintype "bidirectional"))
      (node (ref "R8") (pin "2") (pinfunction "2_2") (pintype "passive"))
    )
    (net (code "59") (name "Net-(IC2-D-)") (class "Default")
      (node (ref "IC2") (pin "4") (pinfunction "D-_4") (pintype "bidirectional"))
      (node (ref "R7") (pin "2") (pinfunction "2_2") (pintype "passive"))
    )
    (net (code "60") (name "Net-(IC2-PE3_IUID)") (class "Default")
      (node (ref "IC2") (pin "9") (pinfunction "PE3_IUID_9") (pintype "bidirectional"))
      (node (ref "JP34") (pin "1") (pinfunction "1_1") (pintype "passive"))
    )
    (net (code "61") (name "Net-(IC2-UCAP)") (class "Default")
      (node (ref "C11") (pin "2") (pinfunction "2_2") (pintype "passive"))
      (node (ref "IC2") (pin "7") (pinfunction "UCAP_7") (pintype "power_in"))
    )
    (net (code "62") (name "Net-(IO1-C)") (class "Default")
      (node (ref "IO1") (pin "4") (pinfunction "C_4") (pintype "bidirectional"))
      (node (ref "J1") (pin "D-") (pinfunction "D-_D-") (pintype "bidirectional"))
      (node (ref "R7") (pin "1") (pinfunction "1_1") (pintype "passive"))
    )
    (net (code "63") (name "Net-(IO1-D)") (class "Default")
      (node (ref "IO1") (pin "6") (pinfunction "D_6") (pintype "bidirectional"))
      (node (ref "J1") (pin "D+") (pinfunction "D+_D+") (pintype "bidirectional"))
      (node (ref "R8") (pin "1") (pinfunction "1_1") (pintype "passive"))
    )
    (net (code "64") (name "Net-(IO1-UCC)") (class "Default")
      (node (ref "IO1") (pin "5") (pinfunction "UCC_5") (pintype "bidirectional"))
      (node (ref "J1") (pin "VBUS") (pinfunction "VBUS_VBUS") (pintype "bidirectional"))
    )
    (net (code "65") (name "Net-(JP9-Pad1)") (class "Default")
      (node (ref "JP9") (pin "1") (pinfunction "1_1") (pintype "passive"))
      (node (ref "P1") (pin "MS1") (pinfunction "MS1_MS1") (pintype "input"))
      (node (ref "R2") (pin "1") (pinfunction "1_1") (pintype "passive"))
    )
    (net (code "66") (name "Net-(JP10-Pad1)") (class "Default")
      (node (ref "JP10") (pin "1") (pinfunction "1_1") (pintype "passive"))
      (node (ref "P1") (pin "MS2") (pinfunction "MS2_MS2") (pintype "input"))
    )
    (net (code "67") (name "Net-(JP11-Pad1)") (class "Default")
      (node (ref "JP11") (pin "1") (pinfunction "1_1") (pintype "passive"))
      (node (ref "P1") (pin "MS3") (pinfunction "MS3_MS3") (pintype "input"))
    )
    (net (code "68") (name "Net-(JP12-Pad1)") (class "Default")
      (node (ref "JP12") (pin "1") (pinfunction "1_1") (pintype "passive"))
      (node (ref "P2") (pin "MS1") (pinfunction "MS1_MS1") (pintype "input"))
      (node (ref "R3") (pin "1") (pinfunction "1_1") (pintype "passive"))
    )
    (net (code "69") (name "Net-(JP13-Pad1)") (class "Default")
      (node (ref "JP13") (pin "1") (pinfunction "1_1") (pintype "passive"))
      (node (ref "P2") (pin "MS2") (pinfunction "MS2_MS2") (pintype "input"))
    )
    (net (code "70") (name "Net-(JP14-Pad1)") (class "Default")
      (node (ref "JP14") (pin "1") (pinfunction "1_1") (pintype "passive"))
      (node (ref "P2") (pin "MS3") (pinfunction "MS3_MS3") (pintype "input"))
    )
    (net (code "71") (name "Net-(JP15-Pad1)") (class "Default")
      (node (ref "JP15") (pin "1") (pinfunction "1_1") (pintype "passive"))
      (node (ref "P3") (pin "MS1") (pinfunction "MS1_MS1") (pintype "input"))
      (node (ref "R4") (pin "1") (pinfunction "1_1") (pintype "passive"))
    )
    (net (code "72") (name "Net-(JP16-Pad1)") (class "Default")
      (node (ref "JP16") (pin "1") (pinfunction "1_1") (pintype "passive"))
      (node (ref "P3") (pin "MS2") (pinfunction "MS2_MS2") (pintype "input"))
    )
    (net (code "73") (name "Net-(JP17-Pad1)") (class "Default")
      (node (ref "JP17") (pin "1") (pinfunction "1_1") (pintype "passive"))
      (node (ref "P3") (pin "MS3") (pinfunction "MS3_MS3") (pintype "input"))
    )
    (net (code "74") (name "Net-(JP18-Pad1)") (class "Default")
      (node (ref "JP18") (pin "1") (pinfunction "1_1") (pintype "passive"))
      (node (ref "P4") (pin "MS1") (pinfunction "MS1_MS1") (pintype "input"))
      (node (ref "R5") (pin "1") (pinfunction "1_1") (pintype "passive"))
    )
    (net (code "75") (name "Net-(JP19-Pad1)") (class "Default")
      (node (ref "JP19") (pin "1") (pinfunction "1_1") (pintype "passive"))
      (node (ref "P4") (pin "MS2") (pinfunction "MS2_MS2") (pintype "input"))
    )
    (net (code "76") (name "Net-(JP20-Pad1)") (class "Default")
      (node (ref "JP20") (pin "1") (pinfunction "1_1") (pintype "passive"))
      (node (ref "P4") (pin "MS3") (pinfunction "MS3_MS3") (pintype "input"))
    )
    (net (code "77") (name "Net-(LED1-PadA)") (class "Default")
      (node (ref "LED1") (pin "A") (pinfunction "A_A") (pintype "passive"))
      (node (ref "R1") (pin "1") (pinfunction "1_1") (pintype "passive"))
    )
    (net (code "78") (name "Net-(P1-~{RESET})") (class "Default")
      (node (ref "P1") (pin "!RST") (pinfunction "~{RESET}_!RST") (pintype "input"))
      (node (ref "P1") (pin "!SLP") (pinfunction "~{SLEEP}_!SLP") (pintype "input"))
    )
    (net (code "79") (name "Net-(P2-~{RESET})") (class "Default")
      (node (ref "P2") (pin "!RST") (pinfunction "~{RESET}_!RST") (pintype "input"))
      (node (ref "P2") (pin "!SLP") (pinfunction "~{SLEEP}_!SLP") (pintype "input"))
    )
    (net (code "80") (name "Net-(P3-~{RESET})") (class "Default")
      (node (ref "P3") (pin "!RST") (pinfunction "~{RESET}_!RST") (pintype "input"))
      (node (ref "P3") (pin "!SLP") (pinfunction "~{SLEEP}_!SLP") (pintype "input"))
    )
    (net (code "81") (name "Net-(P4-~{RESET})") (class "Default")
      (node (ref "P4") (pin "!RST") (pinfunction "~{RESET}_!RST") (pintype "input"))
      (node (ref "P4") (pin "!SLP") (pinfunction "~{SLEEP}_!SLP") (pintype "input"))
    )
    (net (code "82") (name "Net-(Q1-G)") (class "Default")
      (node (ref "Q1") (pin "1") (pinfunction "G_1") (pintype "passive"))
      (node (ref "R19") (pin "2") (pinfunction "2_2") (pintype "passive"))
    )
    (net (code "83") (name "Net-(Q2-G)") (class "Default")
      (node (ref "Q2") (pin "1") (pinfunction "G_1") (pintype "passive"))
      (node (ref "R20") (pin "2") (pinfunction "2_2") (pintype "passive"))
    )
    (net (code "84") (name "Net-(Q3-G)") (class "Default")
      (node (ref "Q3") (pin "1") (pinfunction "G_1") (pintype "passive"))
      (node (ref "R21") (pin "2") (pinfunction "2_2") (pintype "passive"))
    )
    (net (code "85") (name "X-MOT-1A") (class "Default")
      (node (ref "P1") (pin "1A") (pinfunction "MOT-1A_1A") (pintype "power_in"))
      (node (ref "SV1") (pin "3") (pinfunction "3_3") (pintype "passive"))
    )
    (net (code "86") (name "X-MOT-1B") (class "Default")
      (node (ref "P1") (pin "1B") (pinfunction "MOT-1B_1B") (pintype "power_in"))
      (node (ref "SV1") (pin "4") (pinfunction "4_4") (pintype "passive"))
    )
    (net (code "87") (name "X-MOT-2A") (class "Default")
      (node (ref "P1") (pin "2A") (pinfunction "MOT-2A_2A") (pintype "power_in"))
      (node (ref "SV1") (pin "1") (pinfunction "1_1") (pintype "passive"))
    )
    (net (code "88") (name "X-MOT-2B") (class "Default")
      (node (ref "P1") (pin "2B") (pinfunction "MOT-2B_2B") (pintype "power_in"))
      (node (ref "SV1") (pin "2") (pinfunction "2_2") (pintype "passive"))
    )
    (net (code "89") (name "X-STOP") (class "Default")
      (node (ref "IC2") (pin "15") (pinfunction "PB5_PCINT5_OC1A_15") (pintype "bidirectional"))
      (node (ref "SV1") (pin "19") (pinfunction "19_19") (pintype "passive"))
    )
    (net (code "90") (name "Y-MOT-1A") (class "Default")
      (node (ref "P2") (pin "1A") (pinfunction "MOT-1A_1A") (pintype "power_in"))
      (node (ref "SV2") (pin "3") (pinfunction "3_3") (pintype "passive"))
    )
    (net (code "91") (name "Y-MOT-1B") (class "Default")
      (node (ref "P2") (pin "1B") (pinfunction "MOT-1B_1B") (pintype "power_in"))
      (node (ref "SV2") (pin "4") (pinfunction "4_4") (pintype "passive"))
    )
    (net (code "92") (name "Y-MOT-2A") (class "Default")
      (node (ref "P2") (pin "2A") (pinfunction "MOT-2A_2A") (pintype "power_in"))
      (node (ref "SV2") (pin "1") (pinfunction "1_1") (pintype "passive"))
    )
    (net (code "93") (name "Y-MOT-2B") (class "Default")
      (node (ref "P2") (pin "2B") (pinfunction "MOT-2B_2B") (pintype "power_in"))
      (node (ref "SV2") (pin "2") (pinfunction "2_2") (pintype "passive"))
    )
    (net (code "94") (name "Y-STOP") (class "Default")
      (node (ref "IC2") (pin "16") (pinfunction "PB6_PCINT6_OC1B_16") (pintype "bidirectional"))
      (node (ref "SV2") (pin "31") (pinfunction "31_31") (pintype "passive"))
    )
    (net (code "95") (name "Z-MOT-1A") (class "Default")
      (node (ref "P3") (pin "1A") (pinfunction "MOT-1A_1A") (pintype "power_in"))
      (node (ref "SV3") (pin "3") (pinfunction "3_3") (pintype "passive"))
      (node (ref "SV3") (pin "7") (pinfunction "7_7") (pintype "passive"))
    )
    (net (code "96") (name "Z-MOT-1B") (class "Default")
      (node (ref "P3") (pin "1B") (pinfunction "MOT-1B_1B") (pintype "power_in"))
      (node (ref "SV3") (pin "4") (pinfunction "4_4") (pintype "passive"))
      (node (ref "SV3") (pin "8") (pinfunction "8_8") (pintype "passive"))
    )
    (net (code "97") (name "Z-MOT-2A") (class "Default")
      (node (ref "P3") (pin "2A") (pinfunction "MOT-2A_2A") (pintype "power_in"))
      (node (ref "SV3") (pin "1") (pinfunction "1_1") (pintype "passive"))
      (node (ref "SV3") (pin "5") (pinfunction "5_5") (pintype "passive"))
    )
    (net (code "98") (name "Z-MOT-2B") (class "Default")
      (node (ref "P3") (pin "2B") (pinfunction "MOT-2B_2B") (pintype "power_in"))
      (node (ref "SV3") (pin "2") (pinfunction "2_2") (pintype "passive"))
      (node (ref "SV3") (pin "6") (pinfunction "6_6") (pintype "passive"))
    )
    (net (code "99") (name "Z-STOP") (class "Default")
      (node (ref "IC2") (pin "17") (pinfunction "PB7_PCINT7_OC0A_OC1C_17") (pintype "bidirectional"))
      (node (ref "SV3") (pin "9") (pinfunction "9_9") (pintype "passive"))
    )
    (net (code "100") (name "unconnected-(H4-MOUNT-PadB3,2)") (class "Default")
      (node (ref "H4") (pin "B3,2") (pinfunction "MOUNT_B3,2") (pintype "passive"))
    )
    (net (code "101") (name "unconnected-(IO1-A-Pad1)") (class "Default")
      (node (ref "IO1") (pin "1") (pinfunction "A_1") (pintype "bidirectional"))
    )
    (net (code "102") (name "unconnected-(IO1-B-Pad3)") (class "Default")
      (node (ref "IO1") (pin "3") (pinfunction "B_3") (pintype "bidirectional"))
    )
    (net (code "103") (name "unconnected-(SV2-Pad33)") (class "Default")
      (node (ref "SV2") (pin "33") (pinfunction "33_33") (pintype "passive"))
    )
    (net (code "104") (name "unconnected-(SV2-Pad34)") (class "Default")
      (node (ref "SV2") (pin "34") (pinfunction "34_34") (pintype "passive"))
    )
    (net (code "105") (name "unconnected-(X1C-S-Pad3)") (class "Default")
      (node (ref "X1") (pin "3") (pinfunction "S_3") (pintype "passive"))
    )
  )
)
